# I2C_DP_Sensor_3.net
KiCad netlist of a schematic drawn in Altium Designer
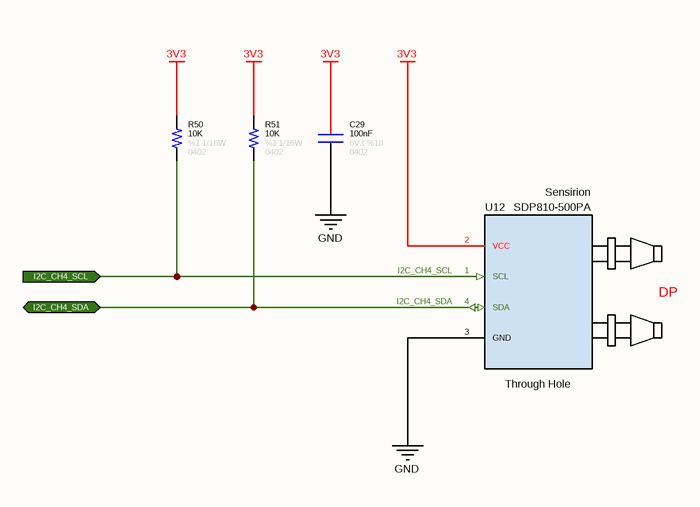
[diagram p0: I2C DP Sensor 3.SchDoc]

(export (version "E")
  (design (tool "Eeschema 10.0.6"))
  (components
    (comp (ref "C29")
      (value "100nF")
      (footprint "CAPACITOR_0402")
      (description "Capacitor - 100nF [0402-6V3] (Ceramic)")
      (fields
        (field (name "MANUFACTURER PART NUMBER") "04026D104KAT4A")
        (field (name "TOLERANCE") "%10")
        (field (name "VOLTAGE") "6V3")
        (field (name "CASE") "0402")
        (field (name "Comment") "Capacitor - 100nF [0402] (Ceramic)")
      )
      (libsource (lib "Akkoyun") (part "Capacitor - 100nF [0402-6V3]"))
    )
    (comp (ref "R50")
      (value "10K")
      (footprint "RESISTOR_0402")
      (description "Thick Film Resistors - SMD 1/16 W 10 KOhm 1%")
      (fields
        (field (name "MANUFACTURER PART NUMBER") "CRCW040210K0FKED")
        (field (name "TOLERANCE") "%1")
        (field (name "CASE") "0402")
        (field (name "POWER") "1/16W")
        (field (name "Comment") "10K - 0402 - %1 - 1/16W")
      )
      (libsource (lib "Akkoyun") (part "Resistor - 10K [0402]"))
    )
    (comp (ref "R51")
      (value "10K")
      (footprint "RESISTOR_0402")
      (description "Thick Film Resistors - SMD 1/16 W 10 KOhm 1%")
      (fields
        (field (name "MANUFACTURER PART NUMBER") "CRCW040210K0FKED")
        (field (name "TOLERANCE") "%1")
        (field (name "CASE") "0402")
        (field (name "POWER") "1/16W")
        (field (name "Comment") "10K - 0402 - %1 - 1/16W")
      )
      (libsource (lib "Akkoyun") (part "Resistor - 10K [0402]"))
    )
    (comp (ref "U12")
      (value "SDP810-500PA")
      (footprint "SDP810-500PA")
      (description "Board Mount Pressure Sensors Tube Connection, I2C , 500Pa")
      (fields
        (field (name "MANUFACTURER NAME") "Sensirion")
        (field (name "MANUFACTURER PART NUMBER") "SDP810-500PA")
        (field (name "CASE") "Through Hole")
      )
      (libsource (lib "Akkoyun") (part "IC - SDP810-500PA"))
    )
  )
  (nets
    (net (code "1") (name "/I2C_CH4_SCL") (class "Default")
      (node (ref "R50") (pin "1") (pinfunction "1_1") (pintype "passive"))
      (node (ref "U12") (pin "1") (pinfunction "SCL_1") (pintype "input"))
    )
    (net (code "2") (name "/I2C_CH4_SDA") (class "Default")
      (node (ref "R51") (pin "1") (pinfunction "1_1") (pintype "passive"))
      (node (ref "U12") (pin "4") (pinfunction "SDA_4") (pintype "bidirectional"))
    )
    (net (code "3") (name "3V3") (class "Default")
      (node (ref "C29") (pin "2") (pinfunction "2_2") (pintype "passive"))
      (node (ref "R50") (pin "2") (pinfunction "2_2") (pintype "passive"))
      (node (ref "R51") (pin "2") (pinfunction "2_2") (pintype "passive"))
      (node (ref "U12") (pin "2") (pinfunction "VCC_2") (pintype "power_in"))
    )
    (net (code "4") (name "GND") (class "Default")
      (node (ref "C29") (pin "1") (pinfunction "1_1") (pintype "passive"))
      (node (ref "U12") (pin "3") (pinfunction "GND_3") (pintype "passive"))
    )
  )
)
